# PushButtonBlack.net
KiCad netlist of a schematic drawn in Altium Designer
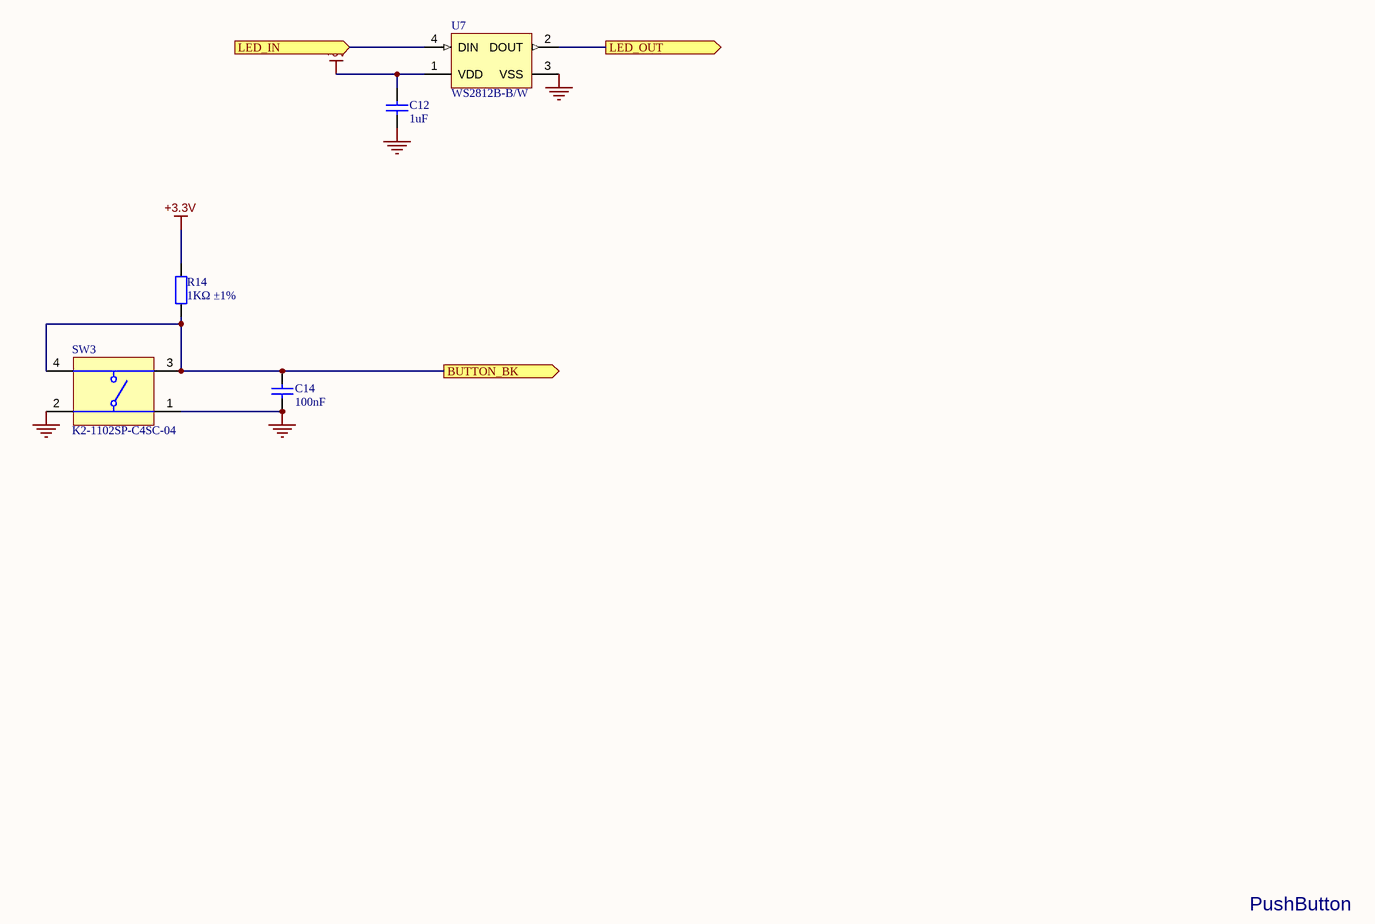
[diagram p0: PushButtonBlack.SchDoc]

(export (version "E")
  (design (tool "Eeschema 10.0.6"))
  (components
    (comp (ref "C12")
      (value "1uF")
      (footprint "0603_C")
      (description "Chip capacitors")
      (fields
        (field (name "MANUFACTURER") "Samsung Electro-Mechanics")
        (field (name "PARTNUMBER") "CL10A105KB8NNNC")
      )
      (libsource (lib "Cap") (part "0603 1uF (105) 10% 50V"))
    )
    (comp (ref "C14")
      (value "100nF")
      (footprint "0603_C")
      (description "Chip capacitors")
      (fields (field (name "MANUFACTURER") "YAGEO") (field (name "PARTNUMBER") "CC0603KRX7R9BB104"))
      (libsource (lib "Cap") (part "0603 100nF (104) 10% 50V"))
    )
    (comp (ref "R14")
      (value "1KΩ ±1%")
      (footprint "0603_R")
      (description "Chip resistor")
      (fields (field (name "MANUFACTURER") "Uniroyal Elec") (field (name "PARTNUMBER") "0603WAF1001T5E"))
      (libsource (lib "RES") (part "0603 1K (1001) 1%"))
    )
    (comp (ref "SW3")
      (value "K2-1102SP-C4SC-04")
      (footprint "TECO-FSM4JSMATR_V")
      (description "Top Actuated 50mA @ 12VDC Round Button SPST 6*6mm Tactile Switches ROHS")
      (libsource (lib "Altium Content Vault") (part "SW-SPST-4_A"))
    )
    (comp (ref "U7")
      (value "WS2812B-B/W")
      (footprint "ADA-RGB-1655_V")
      (fields (field (name "MANUFACTURER") "Worldsemi"))
      (libsource (lib "Altium Content Vault") (part "ADA-RGB-1655-4"))
    )
  )
  (nets
    (net (code "1") (name "+3.3V") (class "Default")
      (node (ref "R14") (pin "1") (pinfunction "1_1") (pintype "passive"))
    )
    (net (code "2") (name "+5V") (class "Default")
      (node (ref "C12") (pin "2") (pinfunction "2_2") (pintype "passive"))
      (node (ref "U7") (pin "1") (pinfunction "VDD_1") (pintype "power_in"))
    )
    (net (code "3") (name "/BUTTON_BK") (class "Default")
      (node (ref "C14") (pin "1") (pinfunction "1_1") (pintype "passive"))
      (node (ref "R14") (pin "2") (pinfunction "2_2") (pintype "passive"))
      (node (ref "SW3") (pin "3") (pinfunction "3_3") (pintype "passive"))
      (node (ref "SW3") (pin "4") (pinfunction "4_4") (pintype "passive"))
    )
    (net (code "4") (name "/LED_IN") (class "Default")
      (node (ref "U7") (pin "4") (pinfunction "DIN_4") (pintype "input"))
    )
    (net (code "5") (name "/LED_OUT") (class "Default")
      (node (ref "U7") (pin "2") (pinfunction "DOUT_2") (pintype "output"))
    )
    (net (code "6") (name "GND") (class "Default")
      (node (ref "C12") (pin "1") (pinfunction "1_1") (pintype "passive"))
      (node (ref "C14") (pin "2") (pinfunction "2_2") (pintype "passive"))
      (node (ref "SW3") (pin "1") (pinfunction "1_1") (pintype "passive"))
      (node (ref "SW3") (pin "2") (pinfunction "2_2") (pintype "passive"))
      (node (ref "U7") (pin "3") (pinfunction "VSS_3") (pintype "power_in"))
    )
  )
)
